# lcdArduinoshield.net
KiCad netlist of a schematic drawn in EAGLE
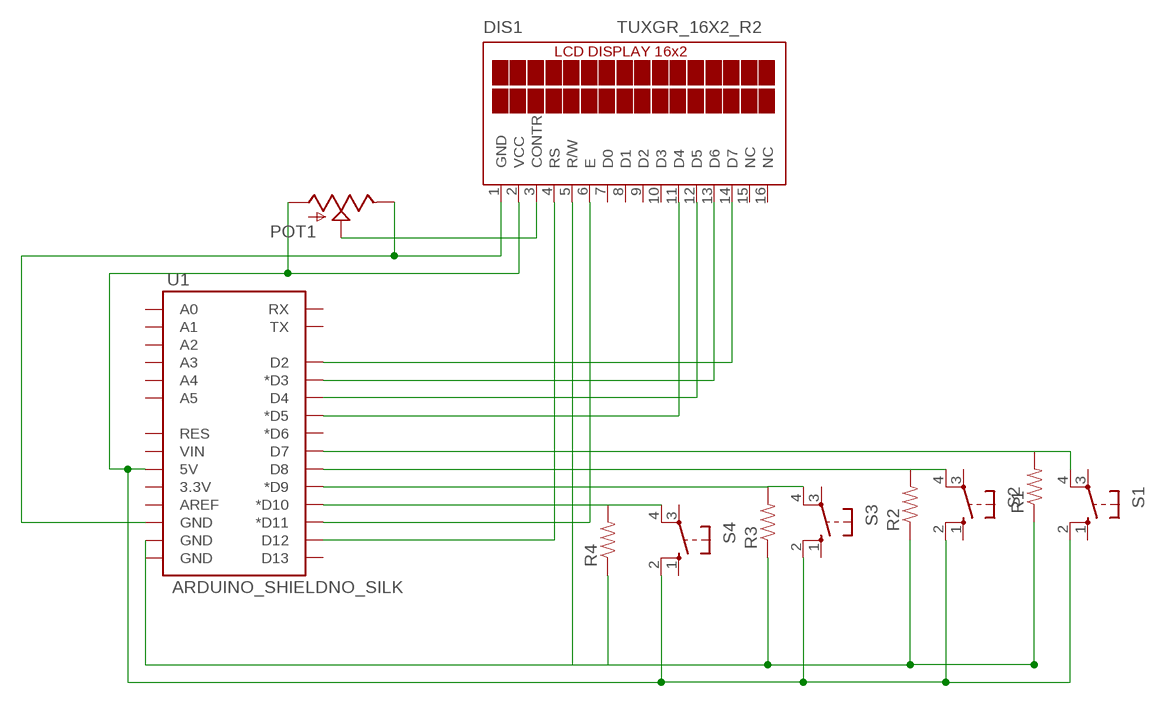
[diagram p0: schematic, sheet 1]

(export (version "E")
  (design (tool "Eeschema 10.0.6"))
  (components
    (comp (ref "DIS1")
      (value "TUXGR_16X2_R2")
      (footprint "eagle-import:TUXGR_16X2_R2")
      (libsource (lib "eagle-import") (part "TUXGR_16X2_R2"))
    )
    (comp (ref "POT1")
      (value "POT100K_3362U")
      (footprint "eagle-import:3362U")
      (libsource (lib "eagle-import") (part "POT100K_3362U"))
    )
    (comp (ref "R1")
      (value "RESISTORPTH-1/4W")
      (footprint "eagle-import:AXIAL-0.4")
      (libsource (lib "eagle-import") (part "RESISTORPTH-1/4W"))
    )
    (comp (ref "R2")
      (value "RESISTORPTH-1/4W")
      (footprint "eagle-import:AXIAL-0.4")
      (libsource (lib "eagle-import") (part "RESISTORPTH-1/4W"))
    )
    (comp (ref "R3")
      (value "RESISTORPTH-1/4W")
      (footprint "eagle-import:AXIAL-0.4")
      (libsource (lib "eagle-import") (part "RESISTORPTH-1/4W"))
    )
    (comp (ref "R4")
      (value "RESISTORPTH-1/4W")
      (footprint "eagle-import:AXIAL-0.4")
      (libsource (lib "eagle-import") (part "RESISTORPTH-1/4W"))
    )
    (comp (ref "S1")
      (value "10-XX")
      (footprint "eagle-import:B3F-10XX")
      (fields (field (name "MPN") "B3F-1000"))
      (libsource (lib "eagle-import") (part "10-XX"))
    )
    (comp (ref "S2")
      (value "10-XX")
      (footprint "eagle-import:B3F-10XX")
      (fields (field (name "MPN") "B3F-1000"))
      (libsource (lib "eagle-import") (part "10-XX"))
    )
    (comp (ref "S3")
      (value "10-XX")
      (footprint "eagle-import:B3F-10XX")
      (fields (field (name "MPN") "B3F-1000"))
      (libsource (lib "eagle-import") (part "10-XX"))
    )
    (comp (ref "S4")
      (value "10-XX")
      (footprint "eagle-import:B3F-10XX")
      (fields (field (name "MPN") "B3F-1000"))
      (libsource (lib "eagle-import") (part "10-XX"))
    )
    (comp (ref "U1")
      (value "ARDUINO_SHIELDNO_SILK")
      (footprint "eagle-import:DUEMILANOVE_VIAS")
      (libsource (lib "eagle-import") (part "ARDUINO_SHIELDNO_SILK"))
    )
  )
  (nets
    (net (code "1") (name "Net-(DIS1-CONTR)") (class "Default")
      (node (ref "DIS1") (pin "3") (pinfunction "CONTR_3") (pintype "input"))
      (node (ref "POT1") (pin "P$2") (pinfunction "S_P$2") (pintype "passive"))
    )
    (net (code "2") (name "Net-(DIS1-D4)") (class "Default")
      (node (ref "DIS1") (pin "11") (pinfunction "D4_11") (pintype "input"))
      (node (ref "U1") (pin "D5") (pinfunction "*D5_D5") (pintype "bidirectional"))
    )
    (net (code "3") (name "Net-(DIS1-D5)") (class "Default")
      (node (ref "DIS1") (pin "12") (pinfunction "D5_12") (pintype "input"))
      (node (ref "U1") (pin "D4") (pinfunction "D4_D4") (pintype "bidirectional"))
    )
    (net (code "4") (name "Net-(DIS1-D6)") (class "Default")
      (node (ref "DIS1") (pin "13") (pinfunction "D6_13") (pintype "input"))
      (node (ref "U1") (pin "D3") (pinfunction "*D3_D3") (pintype "bidirectional"))
    )
    (net (code "5") (name "Net-(DIS1-D7)") (class "Default")
      (node (ref "DIS1") (pin "14") (pinfunction "D7_14") (pintype "input"))
      (node (ref "U1") (pin "D2") (pinfunction "D2_D2") (pintype "bidirectional"))
    )
    (net (code "6") (name "Net-(DIS1-E)") (class "Default")
      (node (ref "DIS1") (pin "6") (pinfunction "E_6") (pintype "input"))
      (node (ref "U1") (pin "D11") (pinfunction "*D11_D11") (pintype "bidirectional"))
    )
    (net (code "7") (name "Net-(DIS1-GND)") (class "Default")
      (node (ref "DIS1") (pin "1") (pinfunction "GND_1") (pintype "power_in"))
      (node (ref "POT1") (pin "P$1") (pinfunction "E_P$1") (pintype "passive"))
      (node (ref "U1") (pin "GND@2") (pinfunction "GND_GND@2") (pintype "bidirectional"))
    )
    (net (code "8") (name "Net-(DIS1-RS)") (class "Default")
      (node (ref "DIS1") (pin "4") (pinfunction "RS_4") (pintype "input"))
      (node (ref "U1") (pin "D12") (pinfunction "D12_D12") (pintype "bidirectional"))
    )
    (net (code "9") (name "Net-(DIS1-R{slash}W)") (class "Default")
      (node (ref "DIS1") (pin "5") (pinfunction "R/W_5") (pintype "input"))
      (node (ref "R1") (pin "P$1") (pinfunction "1_P$1") (pintype "passive"))
      (node (ref "R2") (pin "P$1") (pinfunction "1_P$1") (pintype "passive"))
      (node (ref "R3") (pin "P$1") (pinfunction "1_P$1") (pintype "passive"))
      (node (ref "R4") (pin "P$1") (pinfunction "1_P$1") (pintype "passive"))
      (node (ref "U1") (pin "GND@0") (pinfunction "GND_GND@0") (pintype "bidirectional"))
      (node (ref "U1") (pin "GND@1") (pinfunction "GND_GND@1") (pintype "bidirectional"))
    )
    (net (code "10") (name "Net-(DIS1-VCC)") (class "Default")
      (node (ref "DIS1") (pin "2") (pinfunction "VCC_2") (pintype "power_in"))
      (node (ref "POT1") (pin "P$3") (pinfunction "A_P$3") (pintype "passive"))
      (node (ref "S1") (pin "2") (pinfunction "S1_2") (pintype "passive"))
      (node (ref "S2") (pin "2") (pinfunction "S1_2") (pintype "passive"))
      (node (ref "S3") (pin "2") (pinfunction "S1_2") (pintype "passive"))
      (node (ref "S4") (pin "2") (pinfunction "S1_2") (pintype "passive"))
      (node (ref "U1") (pin "5V") (pinfunction "5V_5V") (pintype "bidirectional"))
    )
    (net (code "11") (name "Net-(R1-2)") (class "Default")
      (node (ref "R1") (pin "P$2") (pinfunction "2_P$2") (pintype "passive"))
      (node (ref "S1") (pin "4") (pinfunction "P1_4") (pintype "passive"))
      (node (ref "U1") (pin "D7") (pinfunction "D7_D7") (pintype "bidirectional"))
    )
    (net (code "12") (name "Net-(R2-2)") (class "Default")
      (node (ref "R2") (pin "P$2") (pinfunction "2_P$2") (pintype "passive"))
      (node (ref "S2") (pin "4") (pinfunction "P1_4") (pintype "passive"))
      (node (ref "U1") (pin "D8") (pinfunction "D8_D8") (pintype "bidirectional"))
    )
    (net (code "13") (name "Net-(R3-2)") (class "Default")
      (node (ref "R3") (pin "P$2") (pinfunction "2_P$2") (pintype "passive"))
      (node (ref "S3") (pin "4") (pinfunction "P1_4") (pintype "passive"))
      (node (ref "U1") (pin "D9") (pinfunction "*D9_D9") (pintype "bidirectional"))
    )
    (net (code "14") (name "Net-(R4-2)") (class "Default")
      (node (ref "R4") (pin "P$2") (pinfunction "2_P$2") (pintype "passive"))
      (node (ref "S4") (pin "4") (pinfunction "P1_4") (pintype "passive"))
      (node (ref "U1") (pin "D10") (pinfunction "*D10_D10") (pintype "bidirectional"))
    )
    (net (code "15") (name "unconnected-(DIS1-D0-Pad7)") (class "Default")
      (node (ref "DIS1") (pin "7") (pinfunction "D0_7") (pintype "input"))
    )
    (net (code "16") (name "unconnected-(DIS1-D1-Pad8)") (class "Default")
      (node (ref "DIS1") (pin "8") (pinfunction "D1_8") (pintype "input"))
    )
    (net (code "17") (name "unconnected-(DIS1-D2-Pad9)") (class "Default")
      (node (ref "DIS1") (pin "9") (pinfunction "D2_9") (pintype "input"))
    )
    (net (code "18") (name "unconnected-(DIS1-D3-Pad10)") (class "Default")
      (node (ref "DIS1") (pin "10") (pinfunction "D3_10") (pintype "input"))
    )
    (net (code "19") (name "unconnected-(DIS1-NC-Pad15)") (class "Default")
      (node (ref "DIS1") (pin "15") (pinfunction "NC_15") (pintype "no_connect"))
    )
    (net (code "20") (name "unconnected-(DIS1-NC-Pad16)") (class "Default")
      (node (ref "DIS1") (pin "16") (pinfunction "NC_16") (pintype "no_connect"))
    )
    (net (code "21") (name "unconnected-(S1-P-Pad3)") (class "Default")
      (node (ref "S1") (pin "3") (pinfunction "P_3") (pintype "passive"))
    )
    (net (code "22") (name "unconnected-(S1-S-Pad1)") (class "Default")
      (node (ref "S1") (pin "1") (pinfunction "S_1") (pintype "passive"))
    )
    (net (code "23") (name "unconnected-(S2-P-Pad3)") (class "Default")
      (node (ref "S2") (pin "3") (pinfunction "P_3") (pintype "passive"))
    )
    (net (code "24") (name "unconnected-(S2-S-Pad1)") (class "Default")
      (node (ref "S2") (pin "1") (pinfunction "S_1") (pintype "passive"))
    )
    (net (code "25") (name "unconnected-(S3-P-Pad3)") (class "Default")
      (node (ref "S3") (pin "3") (pinfunction "P_3") (pintype "passive"))
    )
    (net (code "26") (name "unconnected-(S3-S-Pad1)") (class "Default")
      (node (ref "S3") (pin "1") (pinfunction "S_1") (pintype "passive"))
    )
    (net (code "27") (name "unconnected-(S4-P-Pad3)") (class "Default")
      (node (ref "S4") (pin "3") (pinfunction "P_3") (pintype "passive"))
    )
    (net (code "28") (name "unconnected-(S4-S-Pad1)") (class "Default")
      (node (ref "S4") (pin "1") (pinfunction "S_1") (pintype "passive"))
    )
    (net (code "29") (name "unconnected-(U1-*D6-PadD6)") (class "Default")
      (node (ref "U1") (pin "D6") (pinfunction "*D6_D6") (pintype "bidirectional"))
    )
    (net (code "30") (name "unconnected-(U1-Pad3.3V)") (class "Default")
      (node (ref "U1") (pin "3.3V") (pinfunction "3.3V_3.3V") (pintype "bidirectional"))
    )
    (net (code "31") (name "unconnected-(U1-PadA0)") (class "Default")
      (node (ref "U1") (pin "A0") (pinfunction "A0_A0") (pintype "bidirectional"))
    )
    (net (code "32") (name "unconnected-(U1-PadA1)") (class "Default")
      (node (ref "U1") (pin "A1") (pinfunction "A1_A1") (pintype "bidirectional"))
    )
    (net (code "33") (name "unconnected-(U1-PadA2)") (class "Default")
      (node (ref "U1") (pin "A2") (pinfunction "A2_A2") (pintype "bidirectional"))
    )
    (net (code "34") (name "unconnected-(U1-PadA3)") (class "Default")
      (node (ref "U1") (pin "A3") (pinfunction "A3_A3") (pintype "bidirectional"))
    )
    (net (code "35") (name "unconnected-(U1-PadA4)") (class "Default")
      (node (ref "U1") (pin "A4") (pinfunction "A4_A4") (pintype "bidirectional"))
    )
    (net (code "36") (name "unconnected-(U1-PadA5)") (class "Default")
      (node (ref "U1") (pin "A5") (pinfunction "A5_A5") (pintype "bidirectional"))
    )
    (net (code "37") (name "unconnected-(U1-PadAREF)") (class "Default")
      (node (ref "U1") (pin "AREF") (pinfunction "AREF_AREF") (pintype "bidirectional"))
    )
    (net (code "38") (name "unconnected-(U1-PadD13)") (class "Default")
      (node (ref "U1") (pin "D13") (pinfunction "D13_D13") (pintype "bidirectional"))
    )
    (net (code "39") (name "unconnected-(U1-PadRES)") (class "Default")
      (node (ref "U1") (pin "RES") (pinfunction "RES_RES") (pintype "bidirectional"))
    )
    (net (code "40") (name "unconnected-(U1-PadRX)") (class "Default")
      (node (ref "U1") (pin "RX") (pinfunction "RX_RX") (pintype "bidirectional"))
    )
    (net (code "41") (name "unconnected-(U1-PadTX)") (class "Default")
      (node (ref "U1") (pin "TX") (pinfunction "TX_TX") (pintype "bidirectional"))
    )
    (net (code "42") (name "unconnected-(U1-PadVIN)") (class "Default")
      (node (ref "U1") (pin "VIN") (pinfunction "VIN_VIN") (pintype "bidirectional"))
    )
  )
)
